# SHEET1.net
KiCad netlist of a schematic drawn in Altium Designer
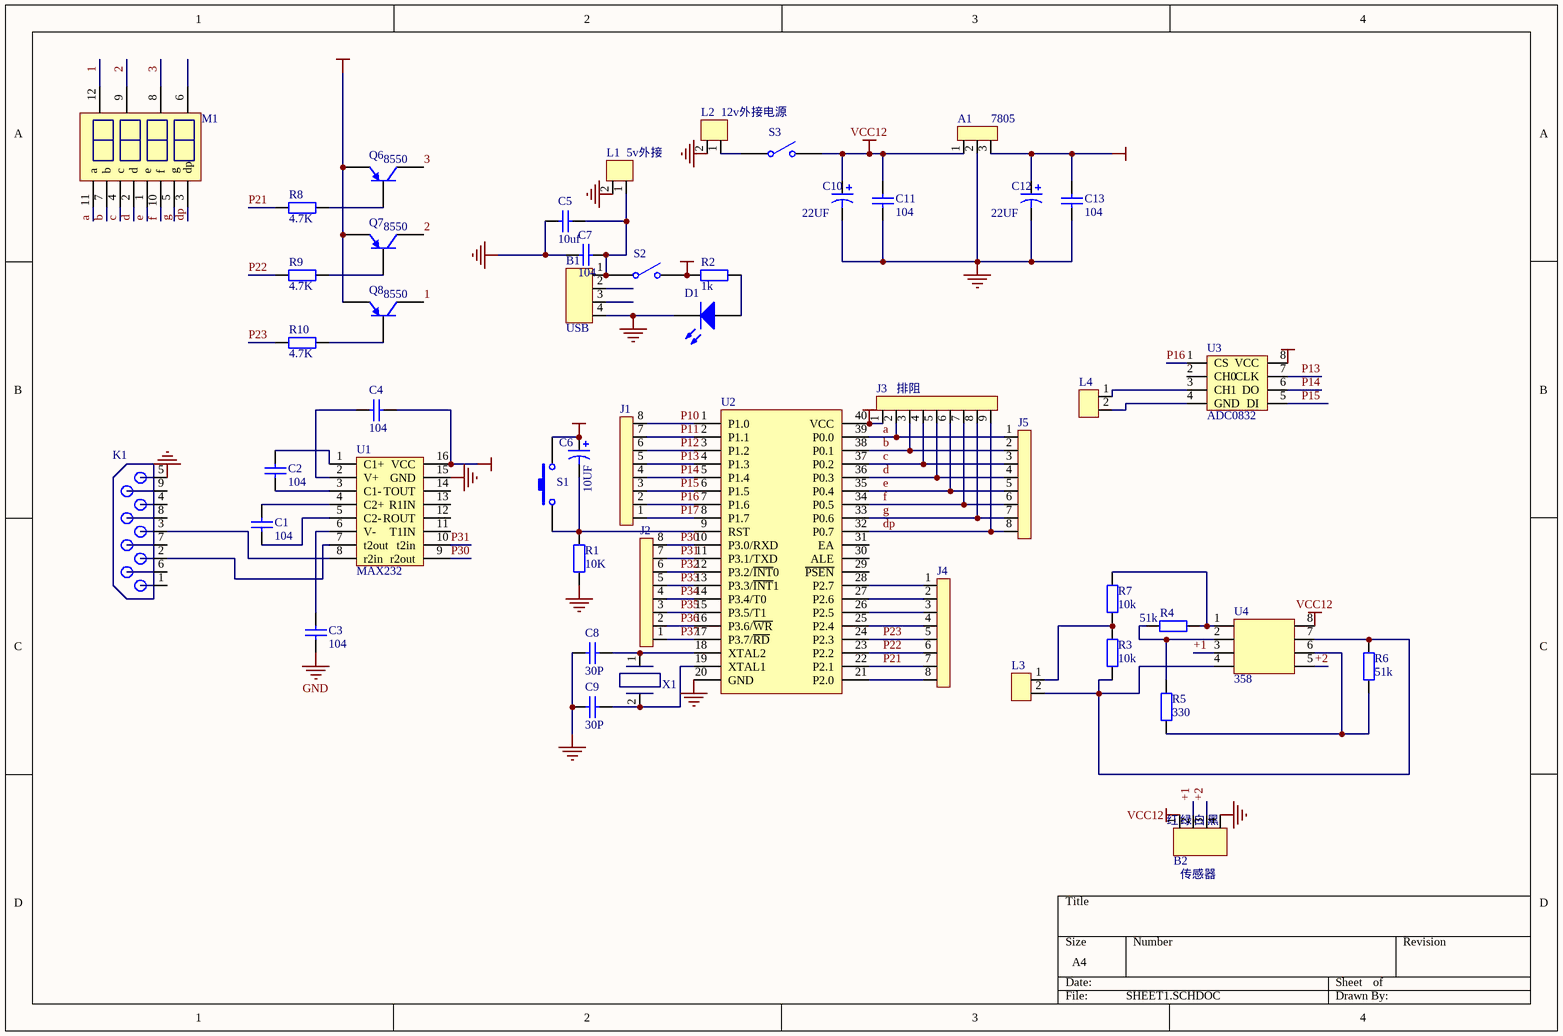
[diagram p0: SHEET1.SCHDOC]

(export (version "E")
  (design (tool "Eeschema 10.0.6"))
  (components
    (comp (ref "A1") (value "7805") (footprint "P-3") (libsource (lib "Schlib1") (part "P-3")))
    (comp (ref "B1") (value "USB") (footprint "USB") (libsource (lib "") (part "USB_1")))
    (comp (ref "B2") (value "传感器") (footprint "P-4") (libsource (lib "Schlib1") (part "USB")))
    (comp (ref "C1")
      (value "104")
      (footprint "P-2")
      (description "Capacitor")
      (fields (field (name "PUBLISHER") "Altium Limited"))
      (libsource (lib "Miscellaneous Devices") (part "Cap"))
    )
    (comp (ref "C2")
      (value "104")
      (footprint "P-2")
      (description "Capacitor")
      (fields (field (name "PUBLISHER") "Altium Limited"))
      (libsource (lib "Miscellaneous Devices") (part "Cap"))
    )
    (comp (ref "C3")
      (value "104")
      (footprint "P-2")
      (description "Capacitor")
      (fields (field (name "PUBLISHER") "Altium Limited"))
      (libsource (lib "Miscellaneous Devices") (part "Cap"))
    )
    (comp (ref "C4")
      (value "104")
      (footprint "P-2")
      (description "Capacitor")
      (fields (field (name "PUBLISHER") "Altium Limited"))
      (libsource (lib "Miscellaneous Devices") (part "Cap"))
    )
    (comp (ref "C5")
      (value "10uf")
      (footprint "P-2")
      (description "Capacitor")
      (fields (field (name "PUBLISHER") "Altium Limited"))
      (libsource (lib "Miscellaneous Devices") (part "Cap"))
    )
    (comp (ref "C6")
      (value "10UF")
      (footprint "P-2有源")
      (description "Polarized Capacitor (Radial)")
      (fields (field (name "PUBLISHER") "Altium Limited"))
      (libsource (lib "Miscellaneous Devices") (part "Cap Pol1"))
    )
    (comp (ref "C7")
      (value "104")
      (footprint "P-2")
      (description "Capacitor")
      (fields (field (name "PUBLISHER") "Altium Limited"))
      (libsource (lib "Miscellaneous Devices") (part "Cap"))
    )
    (comp (ref "C8")
      (value "30P")
      (footprint "P-2")
      (description "Capacitor")
      (fields (field (name "PUBLISHER") "Altium Limited"))
      (libsource (lib "Miscellaneous Devices") (part "Cap"))
    )
    (comp (ref "C9")
      (value "30P")
      (footprint "P-2")
      (description "Capacitor")
      (fields (field (name "PUBLISHER") "Altium Limited"))
      (libsource (lib "Miscellaneous Devices") (part "Cap"))
    )
    (comp (ref "C10")
      (value "22UF")
      (footprint "P-2有源")
      (description "Polarized Capacitor (Radial)")
      (fields (field (name "PUBLISHER") "Altium Limited"))
      (libsource (lib "Miscellaneous Devices") (part "Cap Pol1"))
    )
    (comp (ref "C11")
      (value "104")
      (footprint "P-2")
      (description "Capacitor")
      (fields (field (name "PUBLISHER") "Altium Limited"))
      (libsource (lib "Miscellaneous Devices") (part "Cap"))
    )
    (comp (ref "C12")
      (value "22UF")
      (footprint "P-2有源")
      (description "Polarized Capacitor (Radial)")
      (fields (field (name "PUBLISHER") "Altium Limited"))
      (libsource (lib "Miscellaneous Devices") (part "Cap Pol1"))
    )
    (comp (ref "C13")
      (value "104")
      (footprint "P-2")
      (description "Capacitor")
      (fields (field (name "PUBLISHER") "Altium Limited"))
      (libsource (lib "Miscellaneous Devices") (part "Cap"))
    )
    (comp (ref "D1")
      (value "HLMA-PH00-N0014")
      (footprint "P-2有源")
      (description "Subminiature High Performance AlInGaP Red/Orange LED Lamp")
      (fields (field (name "PUBLISHER") "Altium Limited"))
      (libsource (lib "Agilent Optoelectronic LED") (part "HLMA-PH00-N0014"))
    )
    (comp (ref "J1") (value "P-8") (footprint "P-8") (libsource (lib "") (part "P-8_1")))
    (comp (ref "J2") (value "P-8") (footprint "P-8") (libsource (lib "") (part "P-8_1")))
    (comp (ref "J3") (value "排阻") (footprint "P-9") (libsource (lib "Schlib1") (part "P-9")))
    (comp (ref "J4") (value "P-8") (footprint "P-8") (libsource (lib "51开发板") (part "P-8")))
    (comp (ref "J5") (value "P-8") (footprint "P-8") (libsource (lib "51开发板") (part "P-8")))
    (comp (ref "K1") (value "串口") (footprint "串口") (libsource (lib "Schlib1") (part "串口")))
    (comp (ref "L1") (value "5v外接") (footprint "P-2") (libsource (lib "") (part "P-2_1")))
    (comp (ref "L2") (value "12v外接电源") (footprint "P-2") (libsource (lib "") (part "P-2_1")))
    (comp (ref "L3") (value "12v外接电源") (footprint "P-2") (libsource (lib "51开发板") (part "P-2")))
    (comp (ref "L4") (value "12v外接电源") (footprint "P-2") (libsource (lib "51开发板") (part "P-2")))
    (comp (ref "M1") (value "数码管") (footprint "数码管") (libsource (lib "Schlib1") (part "数码管")))
    (comp (ref "Q6")
      (value "8550")
      (footprint "P-3")
      (description "PNP General Purpose Amplifier")
      (fields (field (name "PUBLISHER") "Altium Limited"))
      (libsource (lib "Miscellaneous Devices") (part "2N3906"))
    )
    (comp (ref "Q7")
      (value "8550")
      (footprint "P-3")
      (description "PNP General Purpose Amplifier")
      (fields (field (name "PUBLISHER") "Altium Limited"))
      (libsource (lib "Miscellaneous Devices") (part "2N3906"))
    )
    (comp (ref "Q8")
      (value "8550")
      (footprint "P-3")
      (description "PNP General Purpose Amplifier")
      (fields (field (name "PUBLISHER") "Altium Limited"))
      (libsource (lib "Miscellaneous Devices") (part "2N3906"))
    )
    (comp (ref "R1")
      (value "10K")
      (footprint "电阻")
      (description "Resistor")
      (fields (field (name "PUBLISHER") "Altium Limited"))
      (libsource (lib "") (part "Res2_2"))
    )
    (comp (ref "R2")
      (value "1k")
      (footprint "电阻")
      (description "Resistor")
      (fields (field (name "PUBLISHER") "Altium Limited"))
      (libsource (lib "") (part "Res2_3"))
    )
    (comp (ref "R3")
      (value "10k")
      (footprint "电阻")
      (description "Resistor")
      (fields (field (name "PUBLISHER") "Altium Limited"))
      (libsource (lib "") (part "Res2_1"))
    )
    (comp (ref "R4")
      (value "51k")
      (footprint "电阻")
      (description "Resistor")
      (fields (field (name "PUBLISHER") "Altium Limited"))
      (libsource (lib "Miscellaneous Devices") (part "Res2"))
    )
    (comp (ref "R5")
      (value "330")
      (footprint "电阻")
      (description "Resistor")
      (fields (field (name "PUBLISHER") "Altium Limited"))
      (libsource (lib "") (part "Res2_2"))
    )
    (comp (ref "R6")
      (value "51k")
      (footprint "电阻")
      (description "Resistor")
      (fields (field (name "PUBLISHER") "Altium Limited"))
      (libsource (lib "") (part "Res2_2"))
    )
    (comp (ref "R7")
      (value "10k")
      (footprint "电阻")
      (description "Resistor")
      (fields (field (name "PUBLISHER") "Altium Limited"))
      (libsource (lib "") (part "Res2_1"))
    )
    (comp (ref "R8")
      (value "4.7K")
      (footprint "电阻")
      (description "Resistor")
      (fields (field (name "PUBLISHER") "Altium Limited"))
      (libsource (lib "Miscellaneous Devices") (part "Res2"))
    )
    (comp (ref "R9")
      (value "4.7K")
      (footprint "电阻")
      (description "Resistor")
      (fields (field (name "PUBLISHER") "Altium Limited"))
      (libsource (lib "Miscellaneous Devices") (part "Res2"))
    )
    (comp (ref "R10")
      (value "4.7K")
      (footprint "电阻")
      (description "Resistor")
      (fields (field (name "PUBLISHER") "Altium Limited"))
      (libsource (lib "Miscellaneous Devices") (part "Res2"))
    )
    (comp (ref "S1")
      (value "SW-PB")
      (footprint "按键")
      (description "Switch")
      (fields (field (name "PUBLISHER") "Altium Limited"))
      (libsource (lib "Miscellaneous Devices") (part "SW-PB"))
    )
    (comp (ref "S2")
      (value "SW-SPST")
      (footprint "LOCK KEY")
      (description "Single-Pole, Single-Throw Switch")
      (fields (field (name "PUBLISHER") "Altium Limited"))
      (libsource (lib "Miscellaneous Devices") (part "SW-SPST"))
    )
    (comp (ref "S3")
      (value "SW-SPST")
      (footprint "LOCK KEY")
      (description "Single-Pole, Single-Throw Switch")
      (fields (field (name "PUBLISHER") "Altium Limited"))
      (libsource (lib "Miscellaneous Devices") (part "SW-SPST"))
    )
    (comp (ref "U1") (value "MAX232") (footprint "DIP-16") (libsource (lib "51开发板") (part "MAX232")))
    (comp (ref "U2") (value "89C52") (footprint "单片机") (libsource (lib "sc") (part "89C52")))
    (comp (ref "U3") (value "ADC0832") (footprint "DIP-8") (libsource (lib "") (part "ADC0832_1")))
    (comp (ref "U4") (value "358") (footprint "DIP-8") (libsource (lib "Schlib1") (part "ADC0832")))
    (comp (ref "X1") (value "晶振") (footprint "晶振") (libsource (lib "Schlib1") (part "晶振")))
  )
  (nets
    (net (code "1") (name "/+1") (class "Default")
      (node (ref "B2") (pin "2") (pinfunction "e_2") (pintype "passive"))
      (node (ref "U4") (pin "3") (pintype "passive"))
    )
    (net (code "2") (name "/+2") (class "Default")
      (node (ref "B2") (pin "3") (pinfunction "e_3") (pintype "passive"))
      (node (ref "U4") (pin "5") (pintype "passive"))
    )
    (net (code "3") (name "/1") (class "Default")
      (node (ref "M1") (pin "12") (pinfunction "dp_12") (pintype "passive"))
      (node (ref "Q8") (pin "3") (pinfunction "C_3") (pintype "passive"))
    )
    (net (code "4") (name "/2") (class "Default")
      (node (ref "M1") (pin "9") (pinfunction "dp_9") (pintype "passive"))
      (node (ref "Q7") (pin "3") (pinfunction "C_3") (pintype "passive"))
    )
    (net (code "5") (name "/3") (class "Default")
      (node (ref "M1") (pin "8") (pinfunction "dp_8") (pintype "passive"))
      (node (ref "Q6") (pin "3") (pinfunction "C_3") (pintype "passive"))
    )
    (net (code "6") (name "/P10") (class "Default")
      (node (ref "J1") (pin "8") (pinfunction "SER_8") (pintype "passive"))
      (node (ref "U2") (pin "1") (pinfunction "P1.0_1") (pintype "passive"))
    )
    (net (code "7") (name "/P11") (class "Default")
      (node (ref "J1") (pin "7") (pinfunction "SER_7") (pintype "passive"))
      (node (ref "U2") (pin "2") (pinfunction "P1.1_2") (pintype "passive"))
    )
    (net (code "8") (name "/P12") (class "Default")
      (node (ref "J1") (pin "6") (pinfunction "SER_6") (pintype "passive"))
      (node (ref "U2") (pin "3") (pinfunction "P1.2_3") (pintype "passive"))
    )
    (net (code "9") (name "/P13") (class "Default")
      (node (ref "J1") (pin "5") (pinfunction "SER_5") (pintype "passive"))
      (node (ref "U2") (pin "4") (pinfunction "P1.3_4") (pintype "passive"))
      (node (ref "U3") (pin "7") (pinfunction "CLK_7") (pintype "passive"))
    )
    (net (code "10") (name "/P14") (class "Default")
      (node (ref "J1") (pin "4") (pinfunction "SER_4") (pintype "passive"))
      (node (ref "U2") (pin "5") (pinfunction "P1.4_5") (pintype "passive"))
      (node (ref "U3") (pin "6") (pinfunction "DO_6") (pintype "passive"))
    )
    (net (code "11") (name "/P15") (class "Default")
      (node (ref "J1") (pin "3") (pinfunction "SER_3") (pintype "passive"))
      (node (ref "U2") (pin "6") (pinfunction "P1.5_6") (pintype "passive"))
      (node (ref "U3") (pin "5") (pinfunction "DI_5") (pintype "passive"))
    )
    (net (code "12") (name "/P16") (class "Default")
      (node (ref "J1") (pin "2") (pinfunction "SER_2") (pintype "passive"))
      (node (ref "U2") (pin "7") (pinfunction "P1.6_7") (pintype "passive"))
      (node (ref "U3") (pin "1") (pinfunction "CS_1") (pintype "passive"))
    )
    (net (code "13") (name "/P17") (class "Default")
      (node (ref "J1") (pin "1") (pinfunction "SER_1") (pintype "passive"))
      (node (ref "U2") (pin "8") (pinfunction "P1.7_8") (pintype "passive"))
    )
    (net (code "14") (name "/P21") (class "Default")
      (node (ref "J4") (pin "7") (pinfunction "SER_7") (pintype "passive"))
      (node (ref "R8") (pin "2") (pinfunction "2_2") (pintype "passive"))
      (node (ref "U2") (pin "22") (pinfunction "P2.1_22") (pintype "passive"))
    )
    (net (code "15") (name "/P22") (class "Default")
      (node (ref "J4") (pin "6") (pinfunction "SER_6") (pintype "passive"))
      (node (ref "R9") (pin "2") (pinfunction "2_2") (pintype "passive"))
      (node (ref "U2") (pin "23") (pinfunction "P2.2_23") (pintype "passive"))
    )
    (net (code "16") (name "/P23") (class "Default")
      (node (ref "J4") (pin "5") (pinfunction "SER_5") (pintype "passive"))
      (node (ref "R10") (pin "2") (pinfunction "2_2") (pintype "passive"))
      (node (ref "U2") (pin "24") (pinfunction "P2.3_24") (pintype "passive"))
    )
    (net (code "17") (name "/P30") (class "Default")
      (node (ref "J2") (pin "8") (pinfunction "SER_8") (pintype "passive"))
      (node (ref "U1") (pin "9") (pinfunction "r2out_9") (pintype "passive"))
      (node (ref "U2") (pin "10") (pinfunction "P3.0/RXD_10") (pintype "passive"))
    )
    (net (code "18") (name "/P31") (class "Default")
      (node (ref "J2") (pin "7") (pinfunction "SER_7") (pintype "passive"))
      (node (ref "U1") (pin "10") (pinfunction "t2in_10") (pintype "passive"))
      (node (ref "U2") (pin "11") (pinfunction "P3.1/TXD_11") (pintype "passive"))
    )
    (net (code "19") (name "/P32") (class "Default")
      (node (ref "J2") (pin "6") (pinfunction "SER_6") (pintype "passive"))
      (node (ref "U2") (pin "12") (pinfunction "P3.2/~{INT}0_12") (pintype "passive"))
    )
    (net (code "20") (name "/P33") (class "Default")
      (node (ref "J2") (pin "5") (pinfunction "SER_5") (pintype "passive"))
      (node (ref "U2") (pin "13") (pinfunction "P3.3/~{INT}1_13") (pintype "passive"))
    )
    (net (code "21") (name "/P34") (class "Default")
      (node (ref "J2") (pin "4") (pinfunction "SER_4") (pintype "passive"))
      (node (ref "U2") (pin "14") (pinfunction "P3.4/T0_14") (pintype "passive"))
    )
    (net (code "22") (name "/P35") (class "Default")
      (node (ref "J2") (pin "3") (pinfunction "SER_3") (pintype "passive"))
      (node (ref "U2") (pin "15") (pinfunction "P3.5/T1_15") (pintype "passive"))
    )
    (net (code "23") (name "/P36") (class "Default")
      (node (ref "J2") (pin "2") (pinfunction "SER_2") (pintype "passive"))
      (node (ref "U2") (pin "16") (pinfunction "P3.6/~{WR}_16") (pintype "passive"))
    )
    (net (code "24") (name "/P37") (class "Default")
      (node (ref "J2") (pin "1") (pinfunction "SER_1") (pintype "passive"))
      (node (ref "U2") (pin "17") (pinfunction "P3.7/~{RD}_17") (pintype "passive"))
    )
    (net (code "25") (name "/a") (class "Default")
      (node (ref "J3") (pin "2") (pinfunction "e_2") (pintype "passive"))
      (node (ref "J5") (pin "1") (pinfunction "SER_1") (pintype "passive"))
      (node (ref "M1") (pin "11") (pinfunction "a_11") (pintype "passive"))
      (node (ref "U2") (pin "39") (pinfunction "P0.0_39") (pintype "passive"))
    )
    (net (code "26") (name "/b") (class "Default")
      (node (ref "J3") (pin "3") (pinfunction "e_3") (pintype "passive"))
      (node (ref "J5") (pin "2") (pinfunction "SER_2") (pintype "passive"))
      (node (ref "M1") (pin "7") (pinfunction "b_7") (pintype "passive"))
      (node (ref "U2") (pin "38") (pinfunction "P0.1_38") (pintype "passive"))
    )
    (net (code "27") (name "/c") (class "Default")
      (node (ref "J3") (pin "4") (pinfunction "e_4") (pintype "passive"))
      (node (ref "J5") (pin "3") (pinfunction "SER_3") (pintype "passive"))
      (node (ref "M1") (pin "4") (pinfunction "c_4") (pintype "passive"))
      (node (ref "U2") (pin "37") (pinfunction "P0.2_37") (pintype "passive"))
    )
    (net (code "28") (name "/d") (class "Default")
      (node (ref "J3") (pin "5") (pinfunction "e_5") (pintype "passive"))
      (node (ref "J5") (pin "4") (pinfunction "SER_4") (pintype "passive"))
      (node (ref "M1") (pin "2") (pinfunction "d_2") (pintype "passive"))
      (node (ref "U2") (pin "36") (pinfunction "P0.3_36") (pintype "passive"))
    )
    (net (code "29") (name "/dp") (class "Default")
      (node (ref "J3") (pin "9") (pinfunction "e_9") (pintype "passive"))
      (node (ref "J5") (pin "8") (pinfunction "SER_8") (pintype "passive"))
      (node (ref "M1") (pin "3") (pinfunction "dp_3") (pintype "passive"))
      (node (ref "U2") (pin "32") (pinfunction "P0.7_32") (pintype "passive"))
    )
    (net (code "30") (name "/e") (class "Default")
      (node (ref "J3") (pin "6") (pinfunction "e_6") (pintype "passive"))
      (node (ref "J5") (pin "5") (pinfunction "SER_5") (pintype "passive"))
      (node (ref "M1") (pin "1") (pinfunction "e_1") (pintype "passive"))
      (node (ref "U2") (pin "35") (pinfunction "P0.4_35") (pintype "passive"))
    )
    (net (code "31") (name "/f") (class "Default")
      (node (ref "J3") (pin "7") (pinfunction "e_7") (pintype "passive"))
      (node (ref "J5") (pin "6") (pinfunction "SER_6") (pintype "passive"))
      (node (ref "M1") (pin "10") (pinfunction "f_10") (pintype "passive"))
      (node (ref "U2") (pin "34") (pinfunction "P0.5_34") (pintype "passive"))
    )
    (net (code "32") (name "/g") (class "Default")
      (node (ref "J3") (pin "8") (pinfunction "e_8") (pintype "passive"))
      (node (ref "J5") (pin "7") (pinfunction "SER_7") (pintype "passive"))
      (node (ref "M1") (pin "5") (pinfunction "g_5") (pintype "passive"))
      (node (ref "U2") (pin "33") (pinfunction "P0.6_33") (pintype "passive"))
    )
    (net (code "33") (name "GND") (class "Default")
      (node (ref "A1") (pin "2") (pinfunction "10_2") (pintype "passive"))
      (node (ref "B1") (pin "4") (pinfunction "e_4") (pintype "passive"))
      (node (ref "B2") (pin "4") (pinfunction "e_4") (pintype "passive"))
      (node (ref "C10") (pin "2") (pinfunction "2_2") (pintype "passive"))
      (node (ref "C11") (pin "1") (pinfunction "1_1") (pintype "passive"))
      (node (ref "C12") (pin "2") (pinfunction "2_2") (pintype "passive"))
      (node (ref "C13") (pin "1") (pinfunction "1_1") (pintype "passive"))
      (node (ref "C3") (pin "1") (pinfunction "1_1") (pintype "passive"))
      (node (ref "C5") (pin "1") (pinfunction "1_1") (pintype "passive"))
      (node (ref "C7") (pin "1") (pinfunction "1_1") (pintype "passive"))
      (node (ref "C8") (pin "1") (pinfunction "1_1") (pintype "passive"))
      (node (ref "C9") (pin "1") (pinfunction "1_1") (pintype "passive"))
      (node (ref "D1") (pin "2") (pinfunction "K_2") (pintype "passive"))
      (node (ref "K1") (pin "5") (pintype "passive"))
      (node (ref "L1") (pin "2") (pinfunction "SER_2") (pintype "passive"))
      (node (ref "L2") (pin "2") (pinfunction "SER_2") (pintype "passive"))
      (node (ref "R1") (pin "1") (pinfunction "1_1") (pintype "passive"))
      (node (ref "U1") (pin "15") (pinfunction "GND_15") (pintype "passive"))
      (node (ref "U2") (pin "20") (pinfunction "GND_20") (pintype "passive"))
    )
    (net (code "34") (name "Net-(D1-A)") (class "Default")
      (node (ref "D1") (pin "1") (pinfunction "A_1") (pintype "passive"))
      (node (ref "R2") (pin "2") (pinfunction "2_2") (pintype "passive"))
    )
    (net (code "35") (name "Net-(L3-SER-Pad1)") (class "Default")
      (node (ref "L3") (pin "1") (pinfunction "SER_1") (pintype "passive"))
      (node (ref "R3") (pin "1") (pinfunction "1_1") (pintype "passive"))
      (node (ref "R7") (pin "2") (pinfunction "2_2") (pintype "passive"))
    )
    (net (code "36") (name "Net-(L3-SER-Pad2)") (class "Default")
      (node (ref "L3") (pin "2") (pinfunction "SER_2") (pintype "passive"))
      (node (ref "R3") (pin "2") (pinfunction "2_2") (pintype "passive"))
      (node (ref "R6") (pin "2") (pinfunction "2_2") (pintype "passive"))
      (node (ref "U4") (pin "4") (pintype "passive"))
      (node (ref "U4") (pin "7") (pintype "passive"))
    )
    (net (code "37") (name "Net-(Q6-B)") (class "Default")
      (node (ref "Q6") (pin "2") (pinfunction "B_2") (pintype "passive"))
      (node (ref "R8") (pin "1") (pinfunction "1_1") (pintype "passive"))
    )
    (net (code "38") (name "Net-(Q7-B)") (class "Default")
      (node (ref "Q7") (pin "2") (pinfunction "B_2") (pintype "passive"))
      (node (ref "R9") (pin "1") (pinfunction "1_1") (pintype "passive"))
    )
    (net (code "39") (name "Net-(Q8-B)") (class "Default")
      (node (ref "Q8") (pin "2") (pinfunction "B_2") (pintype "passive"))
      (node (ref "R10") (pin "1") (pinfunction "1_1") (pintype "passive"))
    )
    (net (code "40") (name "Net-(R4-Pad1)") (class "Default")
      (node (ref "R4") (pin "1") (pinfunction "1_1") (pintype "passive"))
      (node (ref "R7") (pin "1") (pinfunction "1_1") (pintype "passive"))
      (node (ref "U4") (pin "1") (pintype "passive"))
    )
    (net (code "41") (name "Net-(R4-Pad2)") (class "Default")
      (node (ref "R4") (pin "2") (pinfunction "2_2") (pintype "passive"))
      (node (ref "R5") (pin "2") (pinfunction "2_2") (pintype "passive"))
      (node (ref "U4") (pin "2") (pintype "passive"))
    )
    (net (code "42") (name "Net-(R5-Pad1)") (class "Default")
      (node (ref "R5") (pin "1") (pinfunction "1_1") (pintype "passive"))
      (node (ref "R6") (pin "1") (pinfunction "1_1") (pintype "passive"))
      (node (ref "U4") (pin "6") (pintype "passive"))
    )
    (net (code "43") (name "Net-(S2-COMMON)") (class "Default")
      (node (ref "B1") (pin "1") (pinfunction "e_1") (pintype "passive"))
      (node (ref "C5") (pin "2") (pinfunction "2_2") (pintype "passive"))
      (node (ref "C7") (pin "2") (pinfunction "2_2") (pintype "passive"))
      (node (ref "L1") (pin "1") (pinfunction "SER_1") (pintype "passive"))
      (node (ref "S2") (pin "1") (pinfunction "COMMON_1") (pintype "passive"))
    )
    (net (code "44") (name "Net-(S3-COMMON)") (class "Default")
      (node (ref "L2") (pin "1") (pinfunction "SER_1") (pintype "passive"))
      (node (ref "S3") (pin "1") (pinfunction "COMMON_1") (pintype "passive"))
    )
    (net (code "45") (name "Net-(U1-C1+)") (class "Default")
      (node (ref "C2") (pin "1") (pinfunction "1_1") (pintype "passive"))
      (node (ref "U1") (pin "1") (pinfunction "C1+_1") (pintype "passive"))
    )
    (net (code "46") (name "Net-(U1-C1-)") (class "Default")
      (node (ref "C2") (pin "2") (pinfunction "2_2") (pintype "passive"))
      (node (ref "U1") (pin "3") (pinfunction "C1-_3") (pintype "passive"))
    )
    (net (code "47") (name "Net-(U1-C2+)") (class "Default")
      (node (ref "C1") (pin "1") (pinfunction "1_1") (pintype "passive"))
      (node (ref "U1") (pin "4") (pinfunction "C2+_4") (pintype "passive"))
    )
    (net (code "48") (name "Net-(U1-C2-)") (class "Default")
      (node (ref "C1") (pin "2") (pinfunction "2_2") (pintype "passive"))
      (node (ref "U1") (pin "5") (pinfunction "C2-_5") (pintype "passive"))
    )
    (net (code "49") (name "Net-(U1-V+)") (class "Default")
      (node (ref "C4") (pin "1") (pinfunction "1_1") (pintype "passive"))
      (node (ref "U1") (pin "2") (pinfunction "V+_2") (pintype "passive"))
    )
    (net (code "50") (name "Net-(U1-V-)") (class "Default")
      (node (ref "C3") (pin "2") (pinfunction "2_2") (pintype "passive"))
      (node (ref "U1") (pin "6") (pinfunction "V-_6") (pintype "passive"))
    )
    (net (code "51") (name "Net-(U1-r2in)") (class "Default")
      (node (ref "K1") (pin "3") (pintype "passive"))
      (node (ref "U1") (pin "8") (pinfunction "r2in_8") (pintype "passive"))
    )
    (net (code "52") (name "Net-(U1-t2out)") (class "Default")
      (node (ref "K1") (pin "2") (pintype "passive"))
      (node (ref "U1") (pin "7") (pinfunction "t2out_7") (pintype "passive"))
    )
    (net (code "53") (name "Net-(U2-P2.0)") (class "Default")
      (node (ref "J4") (pin "8") (pinfunction "SER_8") (pintype "passive"))
      (node (ref "U2") (pin "21") (pinfunction "P2.0_21") (pintype "passive"))
    )
    (net (code "54") (name "Net-(U2-P2.4)") (class "Default")
      (node (ref "J4") (pin "4") (pinfunction "SER_4") (pintype "passive"))
      (node (ref "U2") (pin "25") (pinfunction "P2.4_25") (pintype "passive"))
    )
    (net (code "55") (name "Net-(U2-P2.5)") (class "Default")
      (node (ref "J4") (pin "3") (pinfunction "SER_3") (pintype "passive"))
      (node (ref "U2") (pin "26") (pinfunction "P2.5_26") (pintype "passive"))
    )
    (net (code "56") (name "Net-(U2-P2.6)") (class "Default")
      (node (ref "J4") (pin "2") (pinfunction "SER_2") (pintype "passive"))
      (node (ref "U2") (pin "27") (pinfunction "P2.6_27") (pintype "passive"))
    )
    (net (code "57") (name "Net-(U2-P2.7)") (class "Default")
      (node (ref "J4") (pin "1") (pinfunction "SER_1") (pintype "passive"))
      (node (ref "U2") (pin "28") (pinfunction "P2.7_28") (pintype "passive"))
    )
    (net (code "58") (name "Net-(U2-RST)") (class "Default")
      (node (ref "C6") (pin "2") (pinfunction "2_2") (pintype "passive"))
      (node (ref "R1") (pin "2") (pinfunction "2_2") (pintype "passive"))
      (node (ref "S1") (pin "1") (pinfunction "1_1") (pintype "passive"))
      (node (ref "U2") (pin "9") (pinfunction "RST_9") (pintype "passive"))
    )
    (net (code "59") (name "Net-(U2-XTAL1)") (class "Default")
      (node (ref "C9") (pin "2") (pinfunction "2_2") (pintype "passive"))
      (node (ref "U2") (pin "19") (pinfunction "XTAL1_19") (pintype "passive"))
      (node (ref "X1") (pin "2") (pinfunction "e_2") (pintype "passive"))
    )
    (net (code "60") (name "Net-(U2-XTAL2)") (class "Default")
      (node (ref "C8") (pin "2") (pinfunction "2_2") (pintype "passive"))
      (node (ref "U2") (pin "18") (pinfunction "XTAL2_18") (pintype "passive"))
      (node (ref "X1") (pin "1") (pinfunction "e_1") (pintype "passive"))
    )
    (net (code "61") (name "Net-(U3-CH1)") (class "Default")
      (node (ref "L4") (pin "1") (pinfunction "SER_1") (pintype "passive"))
      (node (ref "U3") (pin "3") (pinfunction "CH1_3") (pintype "passive"))
    )
    (net (code "62") (name "Net-(U3-GND)") (class "Default")
      (node (ref "L4") (pin "2") (pinfunction "SER_2") (pintype "passive"))
      (node (ref "U3") (pin "4") (pinfunction "GND_4") (pintype "passive"))
    )
    (net (code "63") (name "VCC") (class "Default")
      (node (ref "A1") (pin "3") (pinfunction "11_3") (pintype "passive"))
      (node (ref "C12") (pin "1") (pinfunction "1_1") (pintype "passive"))
      (node (ref "C13") (pin "2") (pinfunction "2_2") (pintype "passive"))
      (node (ref "C4") (pin "2") (pinfunction "2_2") (pintype "passive"))
      (node (ref "C6") (pin "1") (pinfunction "1_1") (pintype "passive"))
      (node (ref "J3") (pin "1") (pinfunction "e_1") (pintype "passive"))
      (node (ref "Q6") (pin "1") (pinfunction "E_1") (pintype "passive"))
      (node (ref "Q7") (pin "1") (pinfunction "E_1") (pintype "passive"))
      (node (ref "Q8") (pin "1") (pinfunction "E_1") (pintype "passive"))
      (node (ref "R2") (pin "1") (pinfunction "1_1") (pintype "passive"))
      (node (ref "S1") (pin "2") (pinfunction "2_2") (pintype "passive"))
      (node (ref "S2") (pin "2") (pinfunction "NO_2") (pintype "passive"))
      (node (ref "U1") (pin "16") (pinfunction "VCC_16") (pintype "passive"))
      (node (ref "U2") (pin "40") (pinfunction "VCC_40") (pintype "passive"))
      (node (ref "U3") (pin "8") (pinfunction "VCC_8") (pintype "passive"))
    )
    (net (code "64") (name "VCC12") (class "Default")
      (node (ref "A1") (pin "1") (pinfunction "9_1") (pintype "passive"))
      (node (ref "B2") (pin "1") (pinfunction "e_1") (pintype "passive"))
      (node (ref "C10") (pin "1") (pinfunction "1_1") (pintype "passive"))
      (node (ref "C11") (pin "2") (pinfunction "2_2") (pintype "passive"))
      (node (ref "S3") (pin "2") (pinfunction "NO_2") (pintype "passive"))
      (node (ref "U4") (pin "8") (pintype "passive"))
    )
    (net (code "65") (name "unconnected-(B1-e-Pad2)") (class "Default")
      (node (ref "B1") (pin "2") (pinfunction "e_2") (pintype "passive"))
    )
    (net (code "66") (name "unconnected-(B1-e-Pad3)") (class "Default")
      (node (ref "B1") (pin "3") (pinfunction "e_3") (pintype "passive"))
    )
    (net (code "67") (name "unconnected-(K1-Pad1)") (class "Default")
      (node (ref "K1") (pin "1") (pintype "passive"))
    )
    (net (code "68") (name "unconnected-(K1-Pad4)") (class "Default")
      (node (ref "K1") (pin "4") (pintype "passive"))
    )
    (net (code "69") (name "unconnected-(K1-Pad6)") (class "Default")
      (node (ref "K1") (pin "6") (pintype "passive"))
    )
    (net (code "70") (name "unconnected-(K1-Pad7)") (class "Default")
      (node (ref "K1") (pin "7") (pintype "passive"))
    )
    (net (code "71") (name "unconnected-(K1-Pad8)") (class "Default")
      (node (ref "K1") (pin "8") (pintype "passive"))
    )
    (net (code "72") (name "unconnected-(K1-Pad9)") (class "Default")
      (node (ref "K1") (pin "9") (pintype "passive"))
    )
    (net (code "73") (name "unconnected-(M1-dp-Pad6)") (class "Default")
      (node (ref "M1") (pin "6") (pinfunction "dp_6") (pintype "passive"))
    )
    (net (code "74") (name "unconnected-(U1-R1IN-Pad13)") (class "Default")
      (node (ref "U1") (pin "13") (pinfunction "R1IN_13") (pintype "passive"))
    )
    (net (code "75") (name "unconnected-(U1-ROUT-Pad12)") (class "Default")
      (node (ref "U1") (pin "12") (pinfunction "ROUT_12") (pintype "passive"))
    )
    (net (code "76") (name "unconnected-(U1-T1IN-Pad11)") (class "Default")
      (node (ref "U1") (pin "11") (pinfunction "T1IN_11") (pintype "passive"))
    )
    (net (code "77") (name "unconnected-(U1-TOUT-Pad14)") (class "Default")
      (node (ref "U1") (pin "14") (pinfunction "TOUT_14") (pintype "passive"))
    )
    (net (code "78") (name "unconnected-(U2-ALE-Pad30)") (class "Default")
      (node (ref "U2") (pin "30") (pinfunction "ALE_30") (pintype "passive"))
    )
    (net (code "79") (name "unconnected-(U2-EA-Pad31)") (class "Default")
      (node (ref "U2") (pin "31") (pinfunction "EA_31") (pintype "passive"))
    )
    (net (code "80") (name "unconnected-(U2-~{PSEN}-Pad29)") (class "Default")
      (node (ref "U2") (pin "29") (pinfunction "~{PSEN}_29") (pintype "passive"))
    )
    (net (code "81") (name "unconnected-(U3-CH0-Pad2)") (class "Default")
      (node (ref "U3") (pin "2") (pinfunction "CH0_2") (pintype "passive"))
    )
  )
)
